# 17_I2C_Sensor_OnBoard.net
KiCad netlist of a schematic drawn in Altium Designer
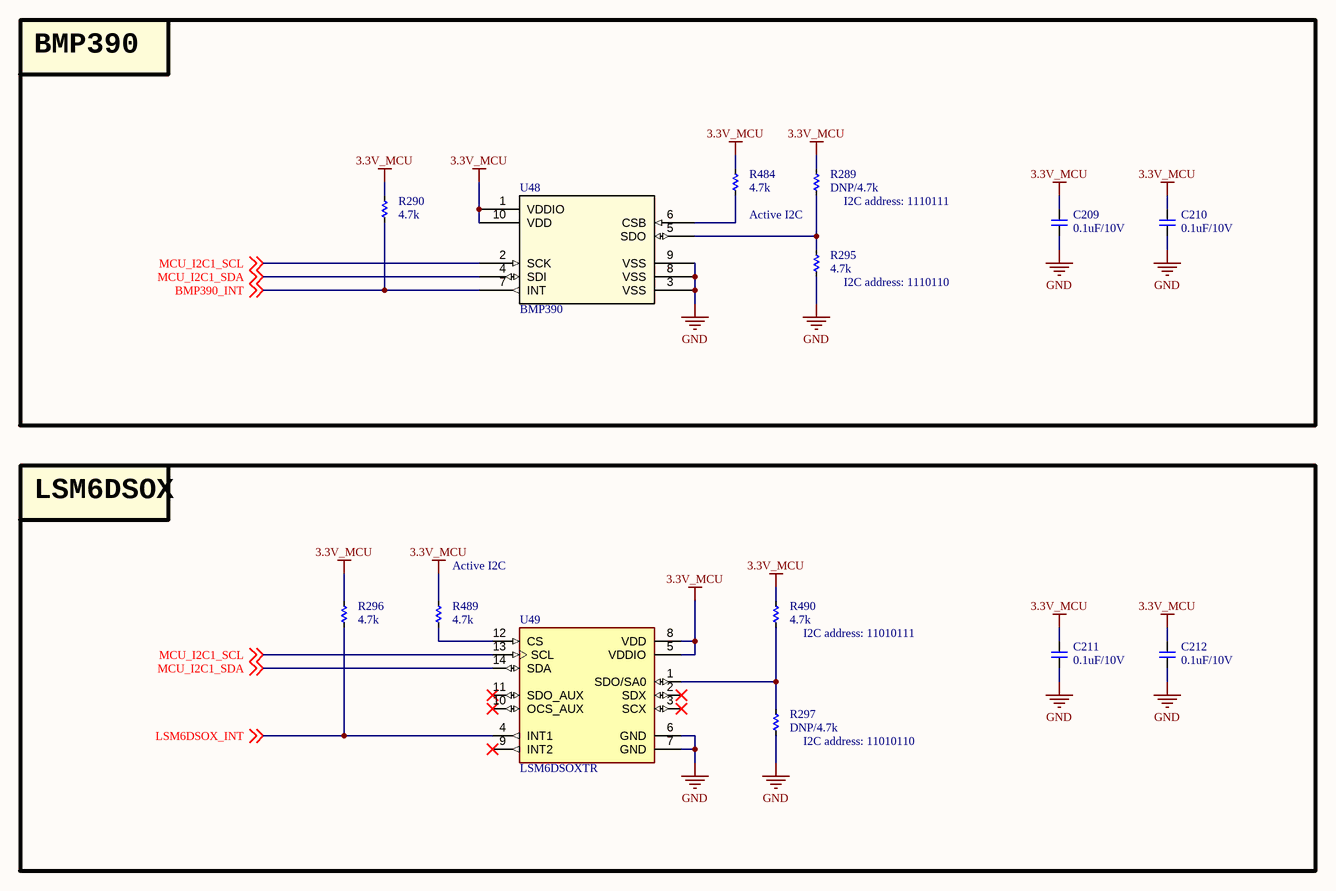
[diagram p0: 17_I2C_Sensor_OnBoard.SchDoc]

(export (version "E")
  (design (tool "Eeschema 10.0.6"))
  (components
    (comp (ref "C209")
      (value "0.1uF/10V")
      (footprint "CAP_C_1005X50_L")
      (description "CAP")
      (libsource (lib "LABLIB") (part "_CAP_C_2"))
    )
    (comp (ref "C210")
      (value "0.1uF/10V")
      (footprint "CAP_C_1005X50_L")
      (description "CAP")
      (libsource (lib "LABLIB") (part "_CAP_C_2"))
    )
    (comp (ref "C211")
      (value "0.1uF/10V")
      (footprint "CAP_C_1005X50_L")
      (description "CAP")
      (libsource (lib "LABLIB") (part "_CAP_C_2"))
    )
    (comp (ref "C212")
      (value "0.1uF/10V")
      (footprint "CAP_C_1005X50_L")
      (description "CAP")
      (libsource (lib "LABLIB") (part "_CAP_C_2"))
    )
    (comp (ref "R289")
      (value "DNP/4.7k")
      (footprint "RES_C_1005x30_L")
      (description "RES")
      (libsource (lib "LABLIB") (part "_RES_B_2"))
    )
    (comp (ref "R290")
      (value "4.7k")
      (footprint "RES_C_0603X30")
      (description "RES")
      (libsource (lib "LABLIB") (part "_RES_B_2"))
    )
    (comp (ref "R295")
      (value "4.7k")
      (footprint "RES_C_1005x30_L")
      (description "RES")
      (libsource (lib "LABLIB") (part "_RES_B_2"))
    )
    (comp (ref "R296")
      (value "4.7k")
      (footprint "RES_C_1005x30_L")
      (description "RES")
      (libsource (lib "LABLIB") (part "_RES_B_2"))
    )
    (comp (ref "R297")
      (value "DNP/4.7k")
      (footprint "RES_C_1005x30_L")
      (description "RES")
      (libsource (lib "LABLIB") (part "_RES_B_2"))
    )
    (comp (ref "R484")
      (value "4.7k")
      (footprint "RES_C_1005x30_L")
      (description "RES")
      (libsource (lib "LABLIB") (part "_RES_B_2"))
    )
    (comp (ref "R489")
      (value "4.7k")
      (footprint "RES_C_1005x30_L")
      (description "RES")
      (libsource (lib "LABLIB") (part "_RES_B_2"))
    )
    (comp (ref "R490")
      (value "4.7k")
      (footprint "RES_C_1005x30_L")
      (description "RES")
      (libsource (lib "LABLIB") (part "_RES_B_2"))
    )
    (comp (ref "U48")
      (value "BMP390")
      (footprint "10LGA_2X2X0p75_BOS")
      (description "Description")
      (fields (field (name "COPYRIGHT") "Copyright (C) 2025 Ultra Librarian. All rights reserved."))
      (libsource (lib "LABLIB") (part "BMP390"))
    )
    (comp (ref "U49")
      (value "LSM6DSOXTR")
      (footprint "PQFN50P250X300X86-14N")
      (description "Accelerometer, Gyroscope, 6 Axis Sensor I2C, SPI Output")
      (fields (field (name "MF") "STMicroelectronics"))
      (libsource (lib "LABLIB") (part "LSM6DSOXTR"))
    )
  )
  (nets
    (net (code "1") (name "3.3V_MCU") (class "Default")
      (node (ref "C209") (pin "2") (pinfunction "2_2") (pintype "passive"))
      (node (ref "C210") (pin "2") (pinfunction "2_2") (pintype "passive"))
      (node (ref "C211") (pin "2") (pinfunction "2_2") (pintype "passive"))
      (node (ref "C212") (pin "2") (pinfunction "2_2") (pintype "passive"))
      (node (ref "R289") (pin "1") (pinfunction "1_1") (pintype "passive"))
      (node (ref "R290") (pin "1") (pinfunction "1_1") (pintype "passive"))
      (node (ref "R296") (pin "1") (pinfunction "1_1") (pintype "passive"))
      (node (ref "R484") (pin "1") (pinfunction "1_1") (pintype "passive"))
      (node (ref "R489") (pin "1") (pinfunction "1_1") (pintype "passive"))
      (node (ref "R490") (pin "1") (pinfunction "1_1") (pintype "passive"))
      (node (ref "U48") (pin "1") (pinfunction "VDDIO_1") (pintype "power_in"))
      (node (ref "U48") (pin "10") (pinfunction "VDD_10") (pintype "power_in"))
      (node (ref "U49") (pin "5") (pinfunction "VDDIO_5") (pintype "power_in"))
      (node (ref "U49") (pin "8") (pinfunction "VDD_8") (pintype "power_in"))
    )
    (net (code "2") (name "BMP390_INT") (class "Default")
      (node (ref "R290") (pin "2") (pinfunction "2_2") (pintype "passive"))
      (node (ref "U48") (pin "7") (pinfunction "INT_7") (pintype "output"))
    )
    (net (code "3") (name "GND") (class "Default")
      (node (ref "C209") (pin "1") (pinfunction "1_1") (pintype "passive"))
      (node (ref "C210") (pin "1") (pinfunction "1_1") (pintype "passive"))
      (node (ref "C211") (pin "1") (pinfunction "1_1") (pintype "passive"))
      (node (ref "C212") (pin "1") (pinfunction "1_1") (pintype "passive"))
      (node (ref "R295") (pin "2") (pinfunction "2_2") (pintype "passive"))
      (node (ref "R297") (pin "2") (pinfunction "2_2") (pintype "passive"))
      (node (ref "U48") (pin "3") (pinfunction "VSS_3") (pintype "power_in"))
      (node (ref "U48") (pin "8") (pinfunction "VSS_8") (pintype "power_in"))
      (node (ref "U48") (pin "9") (pinfunction "VSS_9") (pintype "power_in"))
      (node (ref "U49") (pin "6") (pinfunction "GND_6") (pintype "power_in"))
      (node (ref "U49") (pin "7") (pinfunction "GND_7") (pintype "power_in"))
    )
    (net (code "4") (name "LSM6DSOX_INT") (class "Default")
      (node (ref "R296") (pin "2") (pinfunction "2_2") (pintype "passive"))
      (node (ref "U49") (pin "4") (pinfunction "INT1_4") (pintype "output"))
    )
    (net (code "5") (name "MCU_I2C1_SCL") (class "Default")
      (node (ref "U48") (pin "2") (pinfunction "SCK_2") (pintype "input"))
      (node (ref "U49") (pin "13") (pinfunction "SCL_13") (pintype "input"))
    )
    (net (code "6") (name "MCU_I2C1_SDA") (class "Default")
      (node (ref "U48") (pin "4") (pinfunction "SDI_4") (pintype "bidirectional"))
      (node (ref "U49") (pin "14") (pinfunction "SDA_14") (pintype "bidirectional"))
    )
    (net (code "7") (name "Net-(U48-CSB)") (class "Default")
      (node (ref "R484") (pin "2") (pinfunction "2_2") (pintype "passive"))
      (node (ref "U48") (pin "6") (pinfunction "CSB_6") (pintype "input"))
    )
    (net (code "8") (name "Net-(U48-SDO)") (class "Default")
      (node (ref "R289") (pin "2") (pinfunction "2_2") (pintype "passive"))
      (node (ref "R295") (pin "1") (pinfunction "1_1") (pintype "passive"))
      (node (ref "U48") (pin "5") (pinfunction "SDO_5") (pintype "bidirectional"))
    )
    (net (code "9") (name "Net-(U49-CS)") (class "Default")
      (node (ref "R489") (pin "2") (pinfunction "2_2") (pintype "passive"))
      (node (ref "U49") (pin "12") (pinfunction "CS_12") (pintype "input"))
    )
    (net (code "10") (name "Net-(U49-SDO{slash}SA0)") (class "Default")
      (node (ref "R297") (pin "1") (pinfunction "1_1") (pintype "passive"))
      (node (ref "R490") (pin "2") (pinfunction "2_2") (pintype "passive"))
      (node (ref "U49") (pin "1") (pinfunction "SDO/SA0_1") (pintype "bidirectional"))
    )
    (net (code "11") (name "unconnected-(U49-INT2-Pad9)") (class "Default")
      (node (ref "U49") (pin "9") (pinfunction "INT2_9") (pintype "output+no_connect"))
    )
    (net (code "12") (name "unconnected-(U49-OCS_AUX-Pad10)") (class "Default")
      (node (ref "U49") (pin "10") (pinfunction "OCS_AUX_10") (pintype "bidirectional+no_connect"))
    )
    (net (code "13") (name "unconnected-(U49-SCX-Pad3)") (class "Default")
      (node (ref "U49") (pin "3") (pinfunction "SCX_3") (pintype "bidirectional+no_connect"))
    )
    (net (code "14") (name "unconnected-(U49-SDO_AUX-Pad11)") (class "Default")
      (node (ref "U49") (pin "11") (pinfunction "SDO_AUX_11") (pintype "bidirectional+no_connect"))
    )
    (net (code "15") (name "unconnected-(U49-SDX-Pad2)") (class "Default")
      (node (ref "U49") (pin "2") (pinfunction "SDX_2") (pintype "bidirectional+no_connect"))
    )
  )
)
